# MP3.net
KiCad netlist of a schematic drawn in Altium Designer
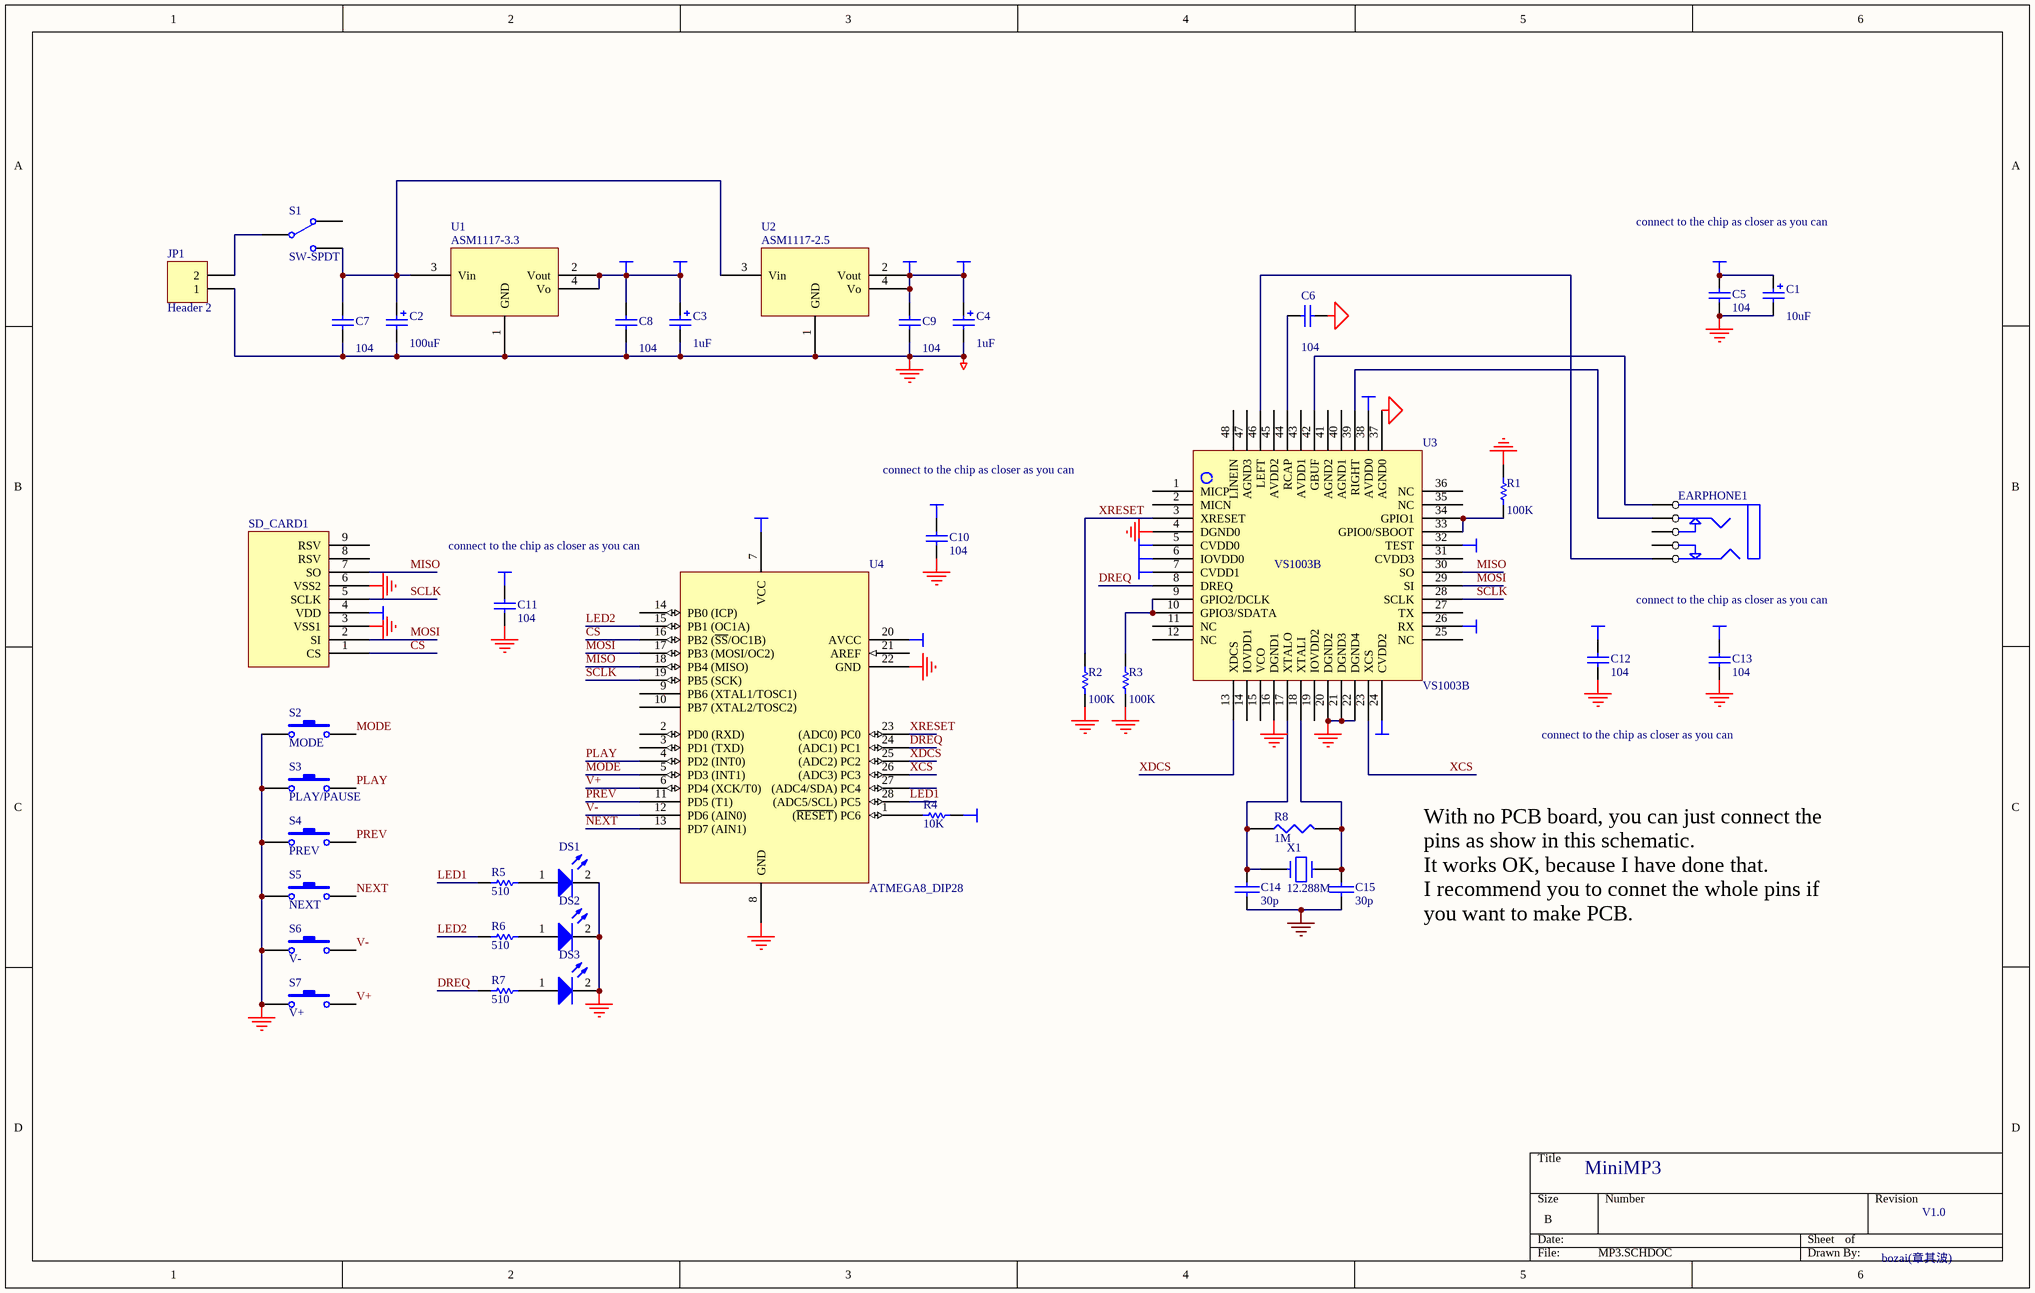
[diagram p0: MP3.SCHDOC]

(export (version "E")
  (design (tool "Eeschema 10.0.6"))
  (components
    (comp (ref "C1")
      (value "Cap Pol1")
      (footprint "RB7.6-15")
      (description "Polarized Capacitor (Radial)")
      (fields
        (field (name "MANUFACTURER") "Generic Components")
        (field (name "ALTIUM_VALUE") "10uF")
        (field (name "PUBLISHER") "Altium Hobart Technology Centre")
      )
      (libsource (lib "Miscellaneous Devices") (part "Cap Pol1"))
    )
    (comp (ref "C2")
      (value "Cap Pol1")
      (footprint "RB7.6-15")
      (description "Polarized Capacitor (Radial)")
      (fields
        (field (name "MANUFACTURER") "Generic Components")
        (field (name "ALTIUM_VALUE") "100uF")
        (field (name "PUBLISHER") "Altium Hobart Technology Centre")
      )
      (libsource (lib "Miscellaneous Devices") (part "Cap Pol1"))
    )
    (comp (ref "C3")
      (value "Cap Pol1")
      (footprint "RB7.6-15")
      (description "Polarized Capacitor (Radial)")
      (fields
        (field (name "MANUFACTURER") "Generic Components")
        (field (name "ALTIUM_VALUE") "1uF")
        (field (name "PUBLISHER") "Altium Hobart Technology Centre")
      )
      (libsource (lib "Miscellaneous Devices") (part "Cap Pol1"))
    )
    (comp (ref "C4")
      (value "Cap Pol1")
      (footprint "RB7.6-15")
      (description "Polarized Capacitor (Radial)")
      (fields
        (field (name "MANUFACTURER") "Generic Components")
        (field (name "ALTIUM_VALUE") "1uF")
        (field (name "PUBLISHER") "Altium Hobart Technology Centre")
      )
      (libsource (lib "Miscellaneous Devices") (part "Cap Pol1"))
    )
    (comp (ref "C5")
      (value "Cap")
      (footprint "RAD-0.3")
      (description "Capacitor")
      (fields
        (field (name "MANUFACTURER") "Generic Components")
        (field (name "ALTIUM_VALUE") "104")
        (field (name "PUBLISHER") "Altium Hobart Technology Centre")
      )
      (libsource (lib "Miscellaneous Devices") (part "Cap"))
    )
    (comp (ref "C6")
      (value "104")
      (footprint "RAD-0.3")
      (description "Capacitor")
      (fields
        (field (name "MANUFACTURER") "Generic Components")
        (field (name "PUBLISHER") "Altium Hobart Technology Centre")
      )
      (libsource (lib "Miscellaneous Devices") (part "Cap"))
    )
    (comp (ref "C7")
      (value "Cap")
      (footprint "RAD-0.3")
      (description "Capacitor")
      (fields
        (field (name "MANUFACTURER") "Generic Components")
        (field (name "ALTIUM_VALUE") "104")
        (field (name "PUBLISHER") "Altium Hobart Technology Centre")
      )
      (libsource (lib "Miscellaneous Devices") (part "Cap"))
    )
    (comp (ref "C8")
      (value "Cap")
      (footprint "RAD-0.3")
      (description "Capacitor")
      (fields
        (field (name "MANUFACTURER") "Generic Components")
        (field (name "ALTIUM_VALUE") "104")
        (field (name "PUBLISHER") "Altium Hobart Technology Centre")
      )
      (libsource (lib "Miscellaneous Devices") (part "Cap"))
    )
    (comp (ref "C9")
      (value "Cap")
      (footprint "RAD-0.3")
      (description "Capacitor")
      (fields
        (field (name "MANUFACTURER") "Generic Components")
        (field (name "ALTIUM_VALUE") "104")
        (field (name "PUBLISHER") "Altium Hobart Technology Centre")
      )
      (libsource (lib "Miscellaneous Devices") (part "Cap"))
    )
    (comp (ref "C10")
      (value "Cap")
      (footprint "RAD-0.3")
      (description "Capacitor")
      (fields
        (field (name "MANUFACTURER") "Generic Components")
        (field (name "ALTIUM_VALUE") "104")
        (field (name "PUBLISHER") "Altium Hobart Technology Centre")
      )
      (libsource (lib "Miscellaneous Devices") (part "Cap"))
    )
    (comp (ref "C11")
      (value "Cap")
      (footprint "RAD-0.3")
      (description "Capacitor")
      (fields
        (field (name "MANUFACTURER") "Generic Components")
        (field (name "ALTIUM_VALUE") "104")
        (field (name "PUBLISHER") "Altium Hobart Technology Centre")
      )
      (libsource (lib "Miscellaneous Devices") (part "Cap"))
    )
    (comp (ref "C12")
      (value "Cap")
      (footprint "RAD-0.3")
      (description "Capacitor")
      (fields
        (field (name "MANUFACTURER") "Generic Components")
        (field (name "ALTIUM_VALUE") "104")
        (field (name "PUBLISHER") "Altium Hobart Technology Centre")
      )
      (libsource (lib "Miscellaneous Devices") (part "Cap"))
    )
    (comp (ref "C13")
      (value "Cap")
      (footprint "RAD-0.3")
      (description "Capacitor")
      (fields
        (field (name "MANUFACTURER") "Generic Components")
        (field (name "ALTIUM_VALUE") "104")
        (field (name "PUBLISHER") "Altium Hobart Technology Centre")
      )
      (libsource (lib "Miscellaneous Devices") (part "Cap"))
    )
    (comp (ref "C14")
      (value "30p")
      (footprint "0805")
      (description "Capacitor")
      (libsource (lib "*") (part "CAP"))
    )
    (comp (ref "C15")
      (value "30p")
      (footprint "0805")
      (description "Capacitor")
      (libsource (lib "*") (part "CAP"))
    )
    (comp (ref "DS1")
      (value "~")
      (footprint "LED-1")
      (description "Typical RED GaAs LED")
      (fields
        (field (name "MANUFACTURER") "Generic Components")
        (field (name "PUBLISHER") "Altium Hobart Technology Centre")
      )
      (libsource (lib "Miscellaneous Devices") (part "LED1"))
    )
    (comp (ref "DS2")
      (value "~")
      (footprint "LED-1")
      (description "Typical RED GaAs LED")
      (fields
        (field (name "MANUFACTURER") "Generic Components")
        (field (name "PUBLISHER") "Altium Hobart Technology Centre")
      )
      (libsource (lib "Miscellaneous Devices") (part "LED1"))
    )
    (comp (ref "DS3")
      (value "~")
      (footprint "LED-1")
      (description "Typical RED GaAs LED")
      (fields
        (field (name "MANUFACTURER") "Generic Components")
        (field (name "PUBLISHER") "Altium Hobart Technology Centre")
      )
      (libsource (lib "Miscellaneous Devices") (part "LED1"))
    )
    (comp (ref "EARPHONE1") (value "~") (footprint "EARHOLE") (libsource (lib "*") (part "MIC")))
    (comp (ref "JP1")
      (value "Header 2")
      (footprint "HDR1X2")
      (description "Header, 2-Pin")
      (fields (field (name "MANUFACTURER") "Generic Components"))
      (libsource (lib "Miscellaneous Connectors") (part "Header 2"))
    )
    (comp (ref "R1")
      (value "Res1")
      (footprint "AXIAL-0.3")
      (description "Resistor")
      (fields
        (field (name "MANUFACTURER") "Generic Components")
        (field (name "ALTIUM_VALUE") "100K")
        (field (name "PUBLISHER") "Altium Hobart Technology Centre")
      )
      (libsource (lib "Miscellaneous Devices") (part "Res1"))
    )
    (comp (ref "R2")
      (value "Res1")
      (footprint "AXIAL-0.3")
      (description "Resistor")
      (fields
        (field (name "MANUFACTURER") "Generic Components")
        (field (name "ALTIUM_VALUE") "100K")
        (field (name "PUBLISHER") "Altium Hobart Technology Centre")
      )
      (libsource (lib "Miscellaneous Devices") (part "Res1"))
    )
    (comp (ref "R3")
      (value "Res1")
      (footprint "AXIAL-0.3")
      (description "Resistor")
      (fields
        (field (name "MANUFACTURER") "Generic Components")
        (field (name "ALTIUM_VALUE") "100K")
        (field (name "PUBLISHER") "Altium Hobart Technology Centre")
      )
      (libsource (lib "Miscellaneous Devices") (part "Res1"))
    )
    (comp (ref "R4")
      (value "Res1")
      (footprint "AXIAL-0.3")
      (description "Resistor")
      (fields
        (field (name "MANUFACTURER") "Generic Components")
        (field (name "ALTIUM_VALUE") "10K")
        (field (name "PUBLISHER") "Altium Hobart Technology Centre")
      )
      (libsource (lib "Miscellaneous Devices") (part "Res1"))
    )
    (comp (ref "R5")
      (value "Res1")
      (footprint "AXIAL-0.3")
      (description "Resistor")
      (fields
        (field (name "MANUFACTURER") "Generic Components")
        (field (name "ALTIUM_VALUE") "510")
        (field (name "PUBLISHER") "Altium Hobart Technology Centre")
      )
      (libsource (lib "Miscellaneous Devices") (part "Res1"))
    )
    (comp (ref "R6")
      (value "Res1")
      (footprint "AXIAL-0.3")
      (description "Resistor")
      (fields
        (field (name "MANUFACTURER") "Generic Components")
        (field (name "ALTIUM_VALUE") "510")
        (field (name "PUBLISHER") "Altium Hobart Technology Centre")
      )
      (libsource (lib "Miscellaneous Devices") (part "Res1"))
    )
    (comp (ref "R7")
      (value "Res1")
      (footprint "AXIAL-0.3")
      (description "Resistor")
      (fields
        (field (name "MANUFACTURER") "Generic Components")
        (field (name "ALTIUM_VALUE") "510")
        (field (name "PUBLISHER") "Altium Hobart Technology Centre")
      )
      (libsource (lib "Miscellaneous Devices") (part "Res1"))
    )
    (comp (ref "R8") (value "1M") (footprint "0805") (libsource (lib "*") (part "RES1")))
    (comp (ref "S1")
      (value "SW-SPDT")
      (footprint "SPDT-3")
      (description "Single-Pole, Double-Throw Switch")
      (fields (field (name "MANUFACTURER") "Generic Components"))
      (libsource (lib "Miscellaneous Devices") (part "SW-SPDT"))
    )
    (comp (ref "S2")
      (value "MODE")
      (footprint "SPST-2")
      (description "Switch")
      (fields (field (name "MANUFACTURER") "Generic Components"))
      (libsource (lib "Miscellaneous Devices") (part "SW-PB"))
    )
    (comp (ref "S3")
      (value "PLAY/PAUSE")
      (footprint "SPST-2")
      (description "Switch")
      (fields (field (name "MANUFACTURER") "Generic Components"))
      (libsource (lib "Miscellaneous Devices") (part "SW-PB"))
    )
    (comp (ref "S4")
      (value "PREV")
      (footprint "SPST-2")
      (description "Switch")
      (fields (field (name "MANUFACTURER") "Generic Components"))
      (libsource (lib "Miscellaneous Devices") (part "SW-PB"))
    )
    (comp (ref "S5")
      (value "NEXT")
      (footprint "SPST-2")
      (description "Switch")
      (fields (field (name "MANUFACTURER") "Generic Components"))
      (libsource (lib "Miscellaneous Devices") (part "SW-PB"))
    )
    (comp (ref "S6")
      (value "V-")
      (footprint "SPST-2")
      (description "Switch")
      (fields (field (name "MANUFACTURER") "Generic Components"))
      (libsource (lib "Miscellaneous Devices") (part "SW-PB"))
    )
    (comp (ref "S7")
      (value "V+")
      (footprint "SPST-2")
      (description "Switch")
      (fields (field (name "MANUFACTURER") "Generic Components"))
      (libsource (lib "Miscellaneous Devices") (part "SW-PB"))
    )
    (comp (ref "SD_CARD1") (value "~") (footprint "SD_CON") (libsource (lib "*") (part "SD_SPI")))
    (comp (ref "U1") (value "ASM1117-3.3") (footprint "SOT223") (libsource (lib "*") (part "LM1084")))
    (comp (ref "U2") (value "ASM1117-2.5") (footprint "SOT223") (libsource (lib "*") (part "LM1084")))
    (comp (ref "U3") (value "VS1003B") (footprint "LQFP48") (libsource (lib "*") (part "ST")))
    (comp (ref "U4")
      (value "ATMEGA8_DIP28")
      (footprint "DIP-28")
      (description "Atmel Microcontroller - Library created by carel..  <www.mpfreezone.com>")
      (libsource (lib "AVR") (part "ATMEGA8_DIP28"))
    )
    (comp (ref "X1")
      (value "12.288M")
      (footprint "CRYSTAL")
      (description "Crystal")
      (libsource (lib "*") (part "CRYSTAL"))
    )
  )
  (nets
    (net (code "1") (name "/CS") (class "Default")
      (node (ref "SD_CARD1") (pin "1") (pinfunction "CS_1") (pintype "passive"))
      (node (ref "U4") (pin "16") (pinfunction "PB2_(~{SS}/OC1B)_16") (pintype "bidirectional"))
    )
    (net (code "2") (name "/DREQ") (class "Default")
      (node (ref "R7") (pin "2") (pinfunction "2_2") (pintype "passive"))
      (node (ref "U3") (pin "8") (pinfunction "DREQ_8") (pintype "passive"))
      (node (ref "U4") (pin "24") (pinfunction "(ADC1)_PC1_24") (pintype "bidirectional"))
    )
    (net (code "3") (name "/LED1") (class "Default")
      (node (ref "R5") (pin "2") (pinfunction "2_2") (pintype "passive"))
      (node (ref "U4") (pin "28") (pinfunction "(ADC5/SCL)_PC5_28") (pintype "bidirectional"))
    )
    (net (code "4") (name "/LED2") (class "Default")
      (node (ref "R6") (pin "2") (pinfunction "2_2") (pintype "passive"))
      (node (ref "U4") (pin "15") (pinfunction "PB1_(OC1A)_15") (pintype "bidirectional"))
    )
    (net (code "5") (name "/MISO") (class "Default")
      (node (ref "SD_CARD1") (pin "7") (pinfunction "SO_7") (pintype "passive"))
      (node (ref "U3") (pin "30") (pinfunction "SO_30") (pintype "passive"))
      (node (ref "U4") (pin "18") (pinfunction "PB4_(MISO)_18") (pintype "bidirectional"))
    )
    (net (code "6") (name "/MODE") (class "Default")
      (node (ref "S2") (pin "2") (pinfunction "2_2") (pintype "passive"))
      (node (ref "U4") (pin "5") (pinfunction "PD3_(INT1)_5") (pintype "bidirectional"))
    )
    (net (code "7") (name "/MOSI") (class "Default")
      (node (ref "SD_CARD1") (pin "2") (pinfunction "SI_2") (pintype "passive"))
      (node (ref "U3") (pin "29") (pinfunction "SI_29") (pintype "passive"))
      (node (ref "U4") (pin "17") (pinfunction "PB3_(MOSI/OC2)_17") (pintype "bidirectional"))
    )
    (net (code "8") (name "/NEXT") (class "Default")
      (node (ref "S5") (pin "2") (pinfunction "2_2") (pintype "passive"))
      (node (ref "U4") (pin "13") (pinfunction "PD7_(AIN1)_13") (pintype "passive"))
    )
    (net (code "9") (name "/PLAY") (class "Default")
      (node (ref "S3") (pin "2") (pinfunction "2_2") (pintype "passive"))
      (node (ref "U4") (pin "4") (pinfunction "PD2_(INT0)_4") (pintype "bidirectional"))
    )
    (net (code "10") (name "/PREV") (class "Default")
      (node (ref "S4") (pin "2") (pinfunction "2_2") (pintype "passive"))
      (node (ref "U4") (pin "11") (pinfunction "PD5_(T1)_11") (pintype "passive"))
    )
    (net (code "11") (name "/SCLK") (class "Default")
      (node (ref "SD_CARD1") (pin "5") (pinfunction "SCLK_5") (pintype "passive"))
      (node (ref "U3") (pin "28") (pinfunction "SCLK_28") (pintype "passive"))
      (node (ref "U4") (pin "19") (pinfunction "PB5_(SCK)_19") (pintype "bidirectional"))
    )
    (net (code "12") (name "/V+") (class "Default")
      (node (ref "S7") (pin "2") (pinfunction "2_2") (pintype "passive"))
      (node (ref "U4") (pin "6") (pinfunction "PD4_(XCK/T0)_6") (pintype "bidirectional"))
    )
    (net (code "13") (name "/V-") (class "Default")
      (node (ref "S6") (pin "2") (pinfunction "2_2") (pintype "passive"))
      (node (ref "U4") (pin "12") (pinfunction "PD6_(AIN0)_12") (pintype "passive"))
    )
    (net (code "14") (name "/XCS") (class "Default")
      (node (ref "U3") (pin "23") (pinfunction "XCS_23") (pintype "passive"))
      (node (ref "U4") (pin "26") (pinfunction "(ADC3)_PC3_26") (pintype "bidirectional"))
    )
    (net (code "15") (name "/XDCS") (class "Default")
      (node (ref "U3") (pin "13") (pinfunction "XDCS_13") (pintype "passive"))
      (node (ref "U4") (pin "25") (pinfunction "(ADC2)_PC2_25") (pintype "bidirectional"))
    )
    (net (code "16") (name "/XRESET") (class "Default")
      (node (ref "R2") (pin "2") (pinfunction "2_2") (pintype "passive"))
      (node (ref "U3") (pin "3") (pinfunction "XRESET_3") (pintype "passive"))
      (node (ref "U4") (pin "23") (pinfunction "(ADC0)_PC0_23") (pintype "bidirectional"))
    )
    (net (code "17") (name "AVDD") (class "Default")
      (node (ref "C1") (pin "1") (pinfunction "1_1") (pintype "passive"))
      (node (ref "C13") (pin "2") (pinfunction "2_2") (pintype "passive"))
      (node (ref "C4") (pin "1") (pinfunction "1_1") (pintype "passive"))
      (node (ref "C5") (pin "2") (pinfunction "2_2") (pintype "passive"))
      (node (ref "C9") (pin "2") (pinfunction "2_2") (pintype "passive"))
      (node (ref "U2") (pin "2") (pinfunction "Vout_2") (pintype "passive"))
      (node (ref "U2") (pin "4") (pinfunction "Vo_4") (pintype "passive"))
      (node (ref "U3") (pin "24") (pinfunction "CVDD2_24") (pintype "passive"))
      (node (ref "U3") (pin "38") (pinfunction "AVDD0_38") (pintype "passive"))
      (node (ref "U3") (pin "5") (pinfunction "CVDD0_5") (pintype "passive"))
      (node (ref "U3") (pin "7") (pinfunction "CVDD1_7") (pintype "passive"))
    )
    (net (code "18") (name "GND") (class "Default")
      (node (ref "C1") (pin "2") (pinfunction "2_2") (pintype "passive"))
      (node (ref "C10") (pin "1") (pinfunction "1_1") (pintype "passive"))
      (node (ref "C11") (pin "1") (pinfunction "1_1") (pintype "passive"))
      (node (ref "C12") (pin "1") (pinfunction "1_1") (pintype "passive"))
      (node (ref "C13") (pin "1") (pinfunction "1_1") (pintype "passive"))
      (node (ref "C14") (pin "2") (pinfunction "2_2") (pintype "passive"))
      (node (ref "C15") (pin "2") (pinfunction "2_2") (pintype "passive"))
      (node (ref "C2") (pin "2") (pinfunction "2_2") (pintype "passive"))
      (node (ref "C3") (pin "2") (pinfunction "2_2") (pintype "passive"))
      (node (ref "C4") (pin "2") (pinfunction "2_2") (pintype "passive"))
      (node (ref "C5") (pin "1") (pinfunction "1_1") (pintype "passive"))
      (node (ref "C6") (pin "1") (pinfunction "1_1") (pintype "passive"))
      (node (ref "C7") (pin "1") (pinfunction "1_1") (pintype "passive"))
      (node (ref "C8") (pin "1") (pinfunction "1_1") (pintype "passive"))
      (node (ref "C9") (pin "1") (pinfunction "1_1") (pintype "passive"))
      (node (ref "DS1") (pin "2") (pinfunction "K_2") (pintype "passive"))
      (node (ref "DS2") (pin "2") (pinfunction "K_2") (pintype "passive"))
      (node (ref "DS3") (pin "2") (pinfunction "K_2") (pintype "passive"))
      (node (ref "JP1") (pin "1") (pinfunction "1_1") (pintype "passive"))
      (node (ref "R1") (pin "2") (pinfunction "2_2") (pintype "passive"))
      (node (ref "R2") (pin "1") (pinfunction "1_1") (pintype "passive"))
      (node (ref "R3") (pin "1") (pinfunction "1_1") (pintype "passive"))
      (node (ref "S2") (pin "1") (pinfunction "1_1") (pintype "passive"))
      (node (ref "S3") (pin "1") (pinfunction "1_1") (pintype "passive"))
      (node (ref "S4") (pin "1") (pinfunction "1_1") (pintype "passive"))
      (node (ref "S5") (pin "1") (pinfunction "1_1") (pintype "passive"))
      (node (ref "S6") (pin "1") (pinfunction "1_1") (pintype "passive"))
      (node (ref "S7") (pin "1") (pinfunction "1_1") (pintype "passive"))
      (node (ref "SD_CARD1") (pin "3") (pinfunction "VSS1_3") (pintype "passive"))
      (node (ref "SD_CARD1") (pin "6") (pinfunction "VSS2_6") (pintype "passive"))
      (node (ref "U1") (pin "1") (pinfunction "GND_1") (pintype "passive"))
      (node (ref "U2") (pin "1") (pinfunction "GND_1") (pintype "passive"))
      (node (ref "U3") (pin "16") (pinfunction "DGND1_16") (pintype "passive"))
      (node (ref "U3") (pin "20") (pinfunction "DGND2_20") (pintype "passive"))
      (node (ref "U3") (pin "21") (pinfunction "DGND3_21") (pintype "passive"))
      (node (ref "U3") (pin "22") (pinfunction "DGND4_22") (pintype "passive"))
      (node (ref "U3") (pin "37") (pinfunction "AGND0_37") (pintype "passive"))
      (node (ref "U3") (pin "4") (pinfunction "DGND0_4") (pintype "passive"))
      (node (ref "U4") (pin "22") (pinfunction "GND_22") (pintype "passive"))
      (node (ref "U4") (pin "8") (pinfunction "GND_8") (pintype "passive"))
    )
    (net (code "19") (name "IOVDD") (class "Default")
      (node (ref "C10") (pin "2") (pinfunction "2_2") (pintype "passive"))
      (node (ref "C11") (pin "2") (pinfunction "2_2") (pintype "passive"))
      (node (ref "C12") (pin "2") (pinfunction "2_2") (pintype "passive"))
      (node (ref "C3") (pin "1") (pinfunction "1_1") (pintype "passive"))
      (node (ref "C8") (pin "2") (pinfunction "2_2") (pintype "passive"))
      (node (ref "R4") (pin "1") (pinfunction "1_1") (pintype "passive"))
      (node (ref "SD_CARD1") (pin "4") (pinfunction "VDD_4") (pintype "passive"))
      (node (ref "U1") (pin "2") (pinfunction "Vout_2") (pintype "passive"))
      (node (ref "U1") (pin "4") (pinfunction "Vo_4") (pintype "passive"))
      (node (ref "U3") (pin "26") (pinfunction "RX_26") (pintype "passive"))
      (node (ref "U3") (pin "32") (pinfunction "TEST_32") (pintype "passive"))
      (node (ref "U3") (pin "6") (pinfunction "IOVDD0_6") (pintype "passive"))
      (node (ref "U4") (pin "20") (pinfunction "AVCC_20") (pintype "passive"))
      (node (ref "U4") (pin "7") (pinfunction "VCC_7") (pintype "passive"))
    )
    (net (code "20") (name "Net-(DS1-A)") (class "Default")
      (node (ref "DS1") (pin "1") (pinfunction "A_1") (pintype "passive"))
      (node (ref "R5") (pin "1") (pinfunction "1_1") (pintype "passive"))
    )
    (net (code "21") (name "Net-(DS2-A)") (class "Default")
      (node (ref "DS2") (pin "1") (pinfunction "A_1") (pintype "passive"))
      (node (ref "R6") (pin "1") (pinfunction "1_1") (pintype "passive"))
    )
    (net (code "22") (name "Net-(DS3-A)") (class "Default")
      (node (ref "DS3") (pin "1") (pinfunction "A_1") (pintype "passive"))
      (node (ref "R7") (pin "1") (pinfunction "1_1") (pintype "passive"))
    )
    (net (code "23") (name "Net-(EARPHONE1-A)") (class "Default")
      (node (ref "EARPHONE1") (pin "1") (pinfunction "A_1") (pintype "passive"))
      (node (ref "U3") (pin "46") (pinfunction "LEFT_46") (pintype "passive"))
    )
    (net (code "24") (name "Net-(EARPHONE1-D)") (class "Default")
      (node (ref "EARPHONE1") (pin "4") (pinfunction "D_4") (pintype "passive"))
      (node (ref "U3") (pin "39") (pinfunction "RIGHT_39") (pintype "passive"))
    )
    (net (code "25") (name "Net-(EARPHONE1-E)") (class "Default")
      (node (ref "EARPHONE1") (pin "5") (pinfunction "E_5") (pintype "passive"))
      (node (ref "U3") (pin "42") (pinfunction "GBUF_42") (pintype "passive"))
    )
    (net (code "26") (name "Net-(S1-COMMON)") (class "Default")
      (node (ref "JP1") (pin "2") (pinfunction "2_2") (pintype "passive"))
      (node (ref "S1") (pin "1") (pinfunction "COMMON_1") (pintype "passive"))
    )
    (net (code "27") (name "Net-(S1-NO)") (class "Default")
      (node (ref "C2") (pin "1") (pinfunction "1_1") (pintype "passive"))
      (node (ref "C7") (pin "2") (pinfunction "2_2") (pintype "passive"))
      (node (ref "S1") (pin "3") (pinfunction "NO_3") (pintype "passive"))
      (node (ref "U1") (pin "3") (pinfunction "Vin_3") (pintype "passive"))
      (node (ref "U2") (pin "3") (pinfunction "Vin_3") (pintype "passive"))
    )
    (net (code "28") (name "Net-(U3-GPIO0{slash}SBOOT)") (class "Default")
      (node (ref "R1") (pin "1") (pinfunction "1_1") (pintype "passive"))
      (node (ref "U3") (pin "33") (pinfunction "GPIO0/SBOOT_33") (pintype "passive"))
      (node (ref "U3") (pin "34") (pinfunction "GPIO1_34") (pintype "passive"))
    )
    (net (code "29") (name "Net-(U3-GPIO2{slash}DCLK)") (class "Default")
      (node (ref "R3") (pin "2") (pinfunction "2_2") (pintype "passive"))
      (node (ref "U3") (pin "10") (pinfunction "GPIO3/SDATA_10") (pintype "passive"))
      (node (ref "U3") (pin "9") (pinfunction "GPIO2/DCLK_9") (pintype "passive"))
    )
    (net (code "30") (name "Net-(U3-RCAP)") (class "Default")
      (node (ref "C6") (pin "2") (pinfunction "2_2") (pintype "passive"))
      (node (ref "U3") (pin "44") (pinfunction "RCAP_44") (pintype "passive"))
    )
    (net (code "31") (name "Net-(U3-XTALI)") (class "Default")
      (node (ref "C15") (pin "1") (pinfunction "1_1") (pintype "passive"))
      (node (ref "R8") (pin "2") (pinfunction "2_2") (pintype "passive"))
      (node (ref "U3") (pin "18") (pinfunction "XTALI_18") (pintype "passive"))
      (node (ref "X1") (pin "1") (pinfunction "1_1") (pintype "passive"))
    )
    (net (code "32") (name "Net-(U3-XTALO)") (class "Default")
      (node (ref "C14") (pin "1") (pinfunction "1_1") (pintype "passive"))
      (node (ref "R8") (pin "1") (pinfunction "1_1") (pintype "passive"))
      (node (ref "U3") (pin "17") (pinfunction "XTALO_17") (pintype "passive"))
      (node (ref "X1") (pin "2") (pinfunction "2_2") (pintype "passive"))
    )
    (net (code "33") (name "Net-(U4-(~{RESET})_PC6)") (class "Default")
      (node (ref "R4") (pin "2") (pinfunction "2_2") (pintype "passive"))
      (node (ref "U4") (pin "1") (pinfunction "(~{RESET})_PC6_1") (pintype "bidirectional"))
    )
    (net (code "34") (name "unconnected-(EARPHONE1-B-Pad2)") (class "Default")
      (node (ref "EARPHONE1") (pin "2") (pinfunction "B_2") (pintype "passive"))
    )
    (net (code "35") (name "unconnected-(EARPHONE1-C-Pad3)") (class "Default")
      (node (ref "EARPHONE1") (pin "3") (pinfunction "C_3") (pintype "passive"))
    )
    (net (code "36") (name "unconnected-(S1-NC-Pad2)") (class "Default")
      (node (ref "S1") (pin "2") (pinfunction "NC_2") (pintype "passive"))
    )
    (net (code "37") (name "unconnected-(SD_CARD1-RSV-Pad8)") (class "Default")
      (node (ref "SD_CARD1") (pin "8") (pinfunction "RSV_8") (pintype "passive"))
    )
    (net (code "38") (name "unconnected-(SD_CARD1-RSV-Pad9)") (class "Default")
      (node (ref "SD_CARD1") (pin "9") (pinfunction "RSV_9") (pintype "passive"))
    )
    (net (code "39") (name "unconnected-(U3-AGND1-Pad40)") (class "Default")
      (node (ref "U3") (pin "40") (pinfunction "AGND1_40") (pintype "passive"))
    )
    (net (code "40") (name "unconnected-(U3-AGND2-Pad41)") (class "Default")
      (node (ref "U3") (pin "41") (pinfunction "AGND2_41") (pintype "passive"))
    )
    (net (code "41") (name "unconnected-(U3-AGND3-Pad47)") (class "Default")
      (node (ref "U3") (pin "47") (pinfunction "AGND3_47") (pintype "passive"))
    )
    (net (code "42") (name "unconnected-(U3-AVDD1-Pad43)") (class "Default")
      (node (ref "U3") (pin "43") (pinfunction "AVDD1_43") (pintype "passive"))
    )
    (net (code "43") (name "unconnected-(U3-AVDD2-Pad45)") (class "Default")
      (node (ref "U3") (pin "45") (pinfunction "AVDD2_45") (pintype "passive"))
    )
    (net (code "44") (name "unconnected-(U3-CVDD3-Pad31)") (class "Default")
      (node (ref "U3") (pin "31") (pinfunction "CVDD3_31") (pintype "passive"))
    )
    (net (code "45") (name "unconnected-(U3-IOVDD1-Pad14)") (class "Default")
      (node (ref "U3") (pin "14") (pinfunction "IOVDD1_14") (pintype "passive"))
    )
    (net (code "46") (name "unconnected-(U3-IOVDD2-Pad19)") (class "Default")
      (node (ref "U3") (pin "19") (pinfunction "IOVDD2_19") (pintype "passive"))
    )
    (net (code "47") (name "unconnected-(U3-LINEIN-Pad48)") (class "Default")
      (node (ref "U3") (pin "48") (pinfunction "LINEIN_48") (pintype "passive"))
    )
    (net (code "48") (name "unconnected-(U3-MICN-Pad2)") (class "Default")
      (node (ref "U3") (pin "2") (pinfunction "MICN_2") (pintype "passive"))
    )
    (net (code "49") (name "unconnected-(U3-MICP-Pad1)") (class "Default")
      (node (ref "U3") (pin "1") (pinfunction "MICP_1") (pintype "passive"))
    )
    (net (code "50") (name "unconnected-(U3-NC-Pad11)") (class "Default")
      (node (ref "U3") (pin "11") (pinfunction "NC_11") (pintype "passive"))
    )
    (net (code "51") (name "unconnected-(U3-NC-Pad12)") (class "Default")
      (node (ref "U3") (pin "12") (pinfunction "NC_12") (pintype "passive"))
    )
    (net (code "52") (name "unconnected-(U3-NC-Pad25)") (class "Default")
      (node (ref "U3") (pin "25") (pinfunction "NC_25") (pintype "passive"))
    )
    (net (code "53") (name "unconnected-(U3-NC-Pad35)") (class "Default")
      (node (ref "U3") (pin "35") (pinfunction "NC_35") (pintype "passive"))
    )
    (net (code "54") (name "unconnected-(U3-NC-Pad36)") (class "Default")
      (node (ref "U3") (pin "36") (pinfunction "NC_36") (pintype "passive"))
    )
    (net (code "55") (name "unconnected-(U3-TX-Pad27)") (class "Default")
      (node (ref "U3") (pin "27") (pinfunction "TX_27") (pintype "passive"))
    )
    (net (code "56") (name "unconnected-(U3-VCO-Pad15)") (class "Default")
      (node (ref "U3") (pin "15") (pinfunction "VCO_15") (pintype "passive"))
    )
    (net (code "57") (name "unconnected-(U4-(ADC4{slash}SDA)_PC4-Pad27)") (class "Default")
      (node (ref "U4") (pin "27") (pinfunction "(ADC4/SDA)_PC4_27") (pintype "bidirectional"))
    )
    (net (code "58") (name "unconnected-(U4-AREF-Pad21)") (class "Default")
      (node (ref "U4") (pin "21") (pinfunction "AREF_21") (pintype "input"))
    )
    (net (code "59") (name "unconnected-(U4-PB0_(ICP)-Pad14)") (class "Default")
      (node (ref "U4") (pin "14") (pinfunction "PB0_(ICP)_14") (pintype "bidirectional"))
    )
    (net (code "60") (name "unconnected-(U4-PB6_(XTAL1{slash}TOSC1)-Pad9)") (class "Default")
      (node (ref "U4") (pin "9") (pinfunction "PB6_(XTAL1/TOSC1)_9") (pintype "passive"))
    )
    (net (code "61") (name "unconnected-(U4-PB7_(XTAL2{slash}TOSC2)-Pad10)") (class "Default")
      (node (ref "U4") (pin "10") (pinfunction "PB7_(XTAL2/TOSC2)_10") (pintype "passive"))
    )
    (net (code "62") (name "unconnected-(U4-PD0_(RXD)-Pad2)") (class "Default")
      (node (ref "U4") (pin "2") (pinfunction "PD0_(RXD)_2") (pintype "bidirectional"))
    )
    (net (code "63") (name "unconnected-(U4-PD1_(TXD)-Pad3)") (class "Default")
      (node (ref "U4") (pin "3") (pinfunction "PD1_(TXD)_3") (pintype "bidirectional"))
    )
  )
)
